# telecommandeB.net
KiCad netlist of a schematic drawn in EAGLE
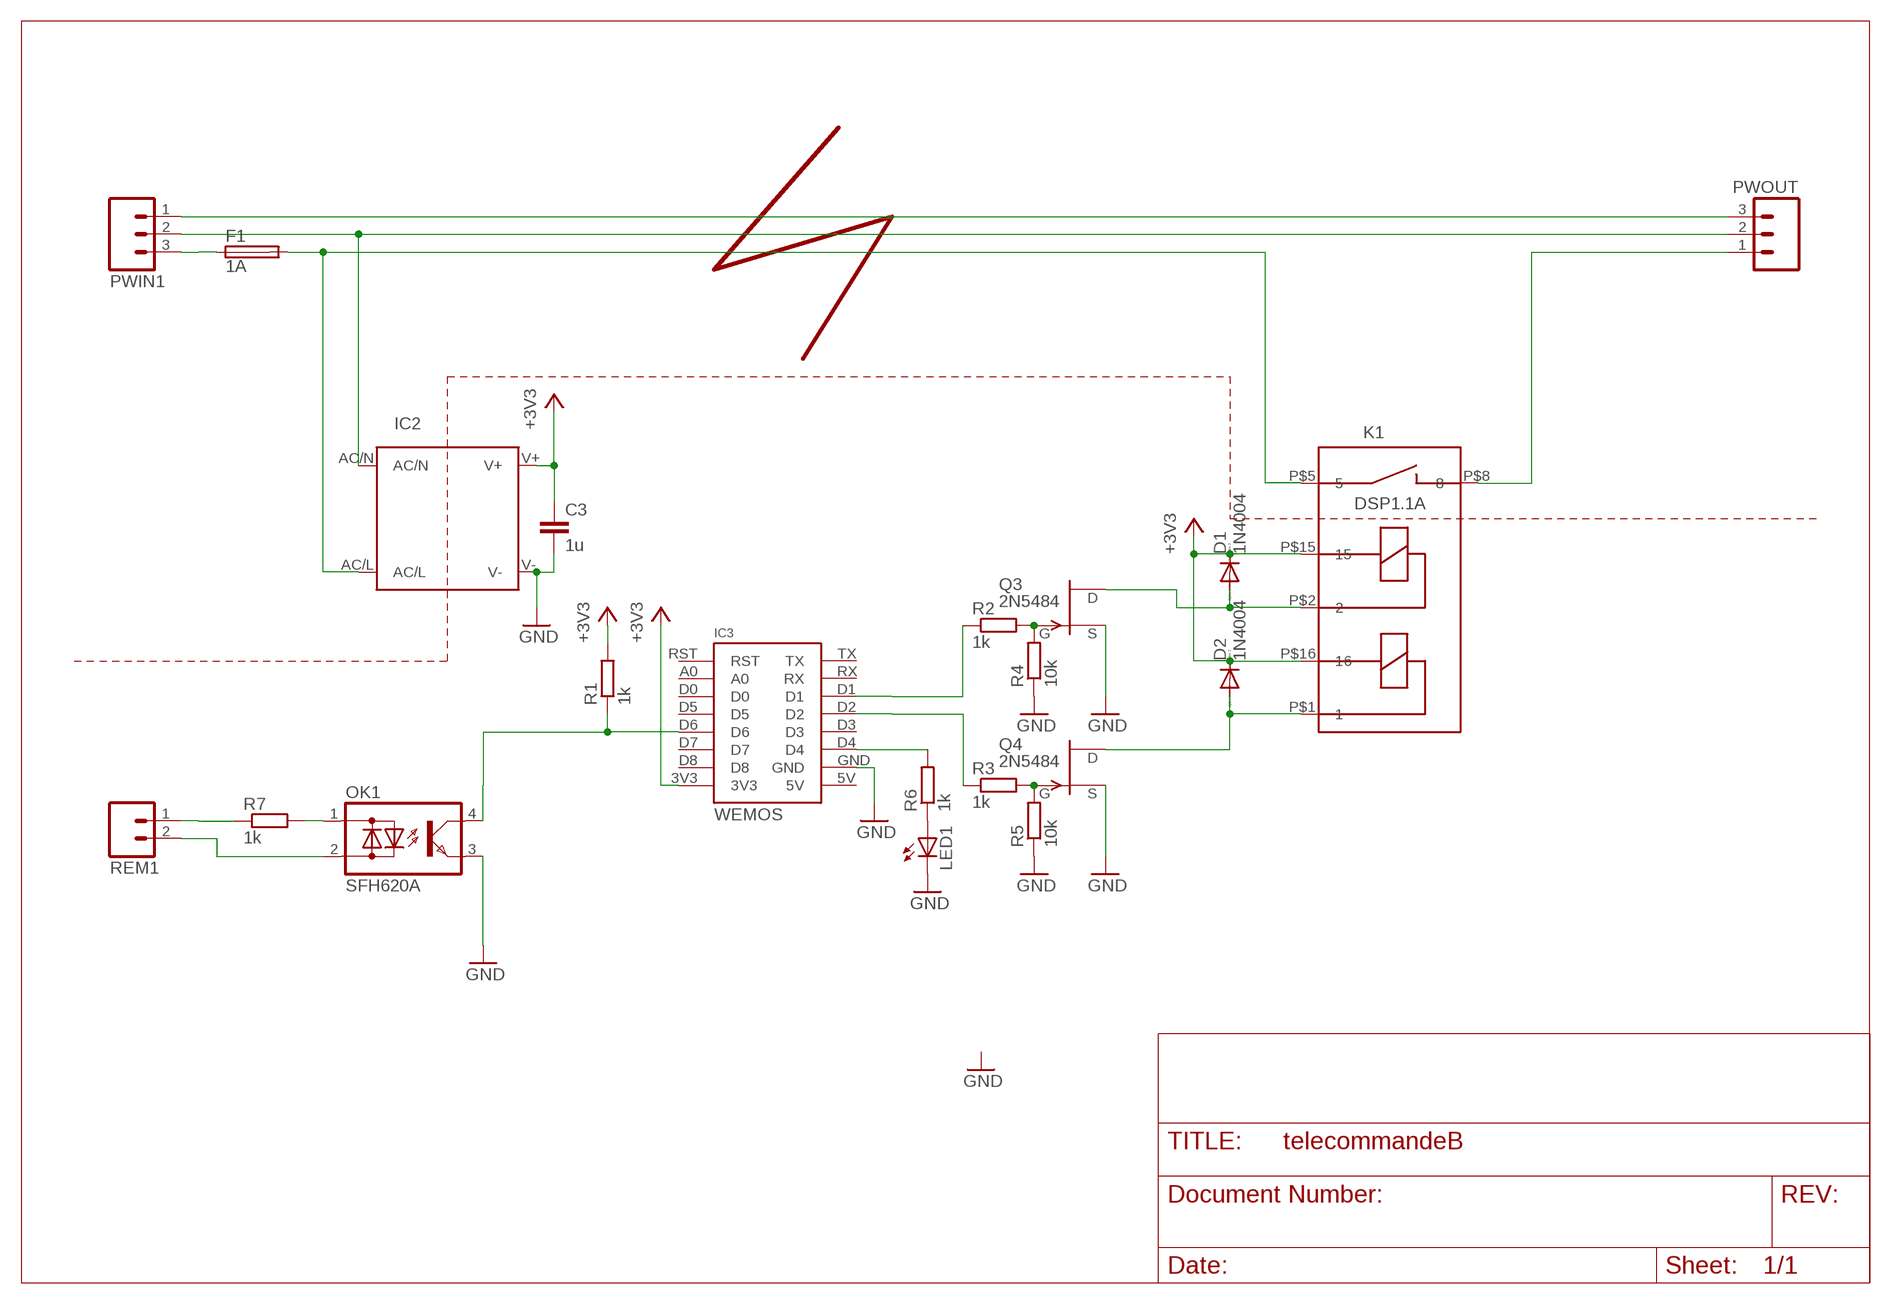
[diagram p0: schematic, sheet 1]

(export (version "E")
  (design (tool "Eeschema 10.0.6"))
  (components
    (comp (ref "C3")
      (value "1u")
      (footprint "eagle-import:C025-024X044")
      (libsource (lib "eagle-import") (part "C-EU025-024X044"))
    )
    (comp (ref "D1")
      (value "1N4004")
      (footprint "eagle-import:DO41-10")
      (libsource (lib "eagle-import") (part "1N4004"))
    )
    (comp (ref "D2")
      (value "1N4004")
      (footprint "eagle-import:DO41-10")
      (libsource (lib "eagle-import") (part "1N4004"))
    )
    (comp (ref "F1")
      (value "1A")
      (footprint "eagle-import:GSH15")
      (fields (field (name "MPN") "64900001039"))
      (libsource (lib "eagle-import") (part "GSH15"))
    )
    (comp (ref "IC2")
      (value "IRM_03")
      (footprint "eagle-import:IRM_03")
      (libsource (lib "eagle-import") (part "IRM_03"))
    )
    (comp (ref "IC3")
      (value "WEMOS")
      (footprint "eagle-import:WEMOS")
      (libsource (lib "eagle-import") (part "WEMOS"))
    )
    (comp (ref "K1")
      (value "DSP1.1A")
      (footprint "eagle-import:DSP1A")
      (libsource (lib "eagle-import") (part "DSP1.1A"))
    )
    (comp (ref "LED1")
      (value "LED3MM")
      (footprint "eagle-import:LED3MM")
      (libsource (lib "eagle-import") (part "LED3MM"))
    )
    (comp (ref "OK1")
      (value "SFH620A")
      (footprint "eagle-import:DIL04")
      (fields (field (name "MPN") "SFH620A-2"))
      (libsource (lib "eagle-import") (part "SFH620A"))
    )
    (comp (ref "PWIN1")
      (value "M03-SCREW-5MM")
      (footprint "eagle-import:SCREWTERMINAL-5MM-3")
      (libsource (lib "eagle-import") (part "M03-SCREW-5MM"))
    )
    (comp (ref "PWOUT")
      (value "M03-SCREW-5MM")
      (footprint "eagle-import:SCREWTERMINAL-5MM-3")
      (libsource (lib "eagle-import") (part "M03-SCREW-5MM"))
    )
    (comp (ref "Q3")
      (value "2N5484")
      (footprint "eagle-import:TO92-")
      (libsource (lib "eagle-import") (part "?5482N4"))
    )
    (comp (ref "Q4")
      (value "2N5484")
      (footprint "eagle-import:TO92-")
      (libsource (lib "eagle-import") (part "?5482N4"))
    )
    (comp (ref "R1")
      (value "1k")
      (footprint "eagle-import:0207_10")
      (libsource (lib "eagle-import") (part "R-EU_0207/10"))
    )
    (comp (ref "R2")
      (value "1k")
      (footprint "eagle-import:0204_7")
      (libsource (lib "eagle-import") (part "R-EU_0204/7"))
    )
    (comp (ref "R3")
      (value "1k")
      (footprint "eagle-import:0204_7")
      (libsource (lib "eagle-import") (part "R-EU_0204/7"))
    )
    (comp (ref "R4")
      (value "10k")
      (footprint "eagle-import:0204_7")
      (libsource (lib "eagle-import") (part "R-EU_0204/7"))
    )
    (comp (ref "R5")
      (value "10k")
      (footprint "eagle-import:0204_7")
      (libsource (lib "eagle-import") (part "R-EU_0204/7"))
    )
    (comp (ref "R6")
      (value "1k")
      (footprint "eagle-import:0204_7")
      (libsource (lib "eagle-import") (part "R-EU_0204/7"))
    )
    (comp (ref "R7")
      (value "1k")
      (footprint "eagle-import:0207_10")
      (libsource (lib "eagle-import") (part "R-EU_0207/10"))
    )
    (comp (ref "REM1")
      (value "M025MM")
      (footprint "eagle-import:SCREWTERMINAL-5MM-2")
      (libsource (lib "eagle-import") (part "M025MM"))
    )
  )
  (nets
    (net (code "1") (name "+3V3") (class "Default")
      (node (ref "C3") (pin "1") (pinfunction "1_1") (pintype "passive"))
      (node (ref "D1") (pin "C") (pinfunction "C_C") (pintype "passive"))
      (node (ref "D2") (pin "C") (pinfunction "C_C") (pintype "passive"))
      (node (ref "IC2") (pin "V+") (pinfunction "V+_V+") (pintype "output"))
      (node (ref "IC3") (pin "3V3") (pinfunction "3V3_3V3") (pintype "bidirectional"))
      (node (ref "K1") (pin "P$15") (pinfunction "15_P$15") (pintype "bidirectional"))
      (node (ref "K1") (pin "P$16") (pinfunction "16_P$16") (pintype "bidirectional"))
      (node (ref "R1") (pin "2") (pinfunction "2_2") (pintype "passive"))
    )
    (net (code "2") (name "GND") (class "Default")
      (node (ref "C3") (pin "2") (pinfunction "2_2") (pintype "passive"))
      (node (ref "IC2") (pin "V-") (pinfunction "V-_V-") (pintype "output"))
      (node (ref "IC3") (pin "GND") (pinfunction "GND_GND") (pintype "bidirectional"))
      (node (ref "LED1") (pin "K") (pinfunction "C_K") (pintype "passive"))
      (node (ref "OK1") (pin "3") (pinfunction "E_3") (pintype "passive"))
      (node (ref "Q3") (pin "2") (pinfunction "S_2") (pintype "passive"))
      (node (ref "Q4") (pin "2") (pinfunction "S_2") (pintype "passive"))
      (node (ref "R4") (pin "1") (pinfunction "1_1") (pintype "passive"))
      (node (ref "R5") (pin "1") (pinfunction "1_1") (pintype "passive"))
    )
    (net (code "3") (name "Net-(F1-Pad1)") (class "Default")
      (node (ref "F1") (pin "1") (pinfunction "1_1") (pintype "passive"))
      (node (ref "PWIN1") (pin "3") (pinfunction "3_3") (pintype "passive"))
    )
    (net (code "4") (name "Net-(IC2-PadAC{slash}N)") (class "Default")
      (node (ref "IC2") (pin "AC/N") (pinfunction "AC/N_AC/N") (pintype "input"))
      (node (ref "PWIN1") (pin "2") (pinfunction "2_2") (pintype "passive"))
      (node (ref "PWOUT") (pin "2") (pinfunction "2_2") (pintype "passive"))
    )
    (net (code "5") (name "Net-(IC3-PadD1)") (class "Default")
      (node (ref "IC3") (pin "D1") (pinfunction "D1_D1") (pintype "bidirectional"))
      (node (ref "R2") (pin "1") (pinfunction "1_1") (pintype "passive"))
    )
    (net (code "6") (name "Net-(IC3-PadD2)") (class "Default")
      (node (ref "IC3") (pin "D2") (pinfunction "D2_D2") (pintype "bidirectional"))
      (node (ref "R3") (pin "1") (pinfunction "1_1") (pintype "passive"))
    )
    (net (code "7") (name "Net-(IC3-PadD4)") (class "Default")
      (node (ref "IC3") (pin "D4") (pinfunction "D4_D4") (pintype "bidirectional"))
      (node (ref "R6") (pin "2") (pinfunction "2_2") (pintype "passive"))
    )
    (net (code "8") (name "Net-(K1-1)") (class "Default")
      (node (ref "D2") (pin "A") (pinfunction "A_A") (pintype "passive"))
      (node (ref "K1") (pin "P$1") (pinfunction "1_P$1") (pintype "bidirectional"))
      (node (ref "Q4") (pin "3") (pinfunction "D_3") (pintype "passive"))
    )
    (net (code "9") (name "Net-(K1-2)") (class "Default")
      (node (ref "D1") (pin "A") (pinfunction "A_A") (pintype "passive"))
      (node (ref "K1") (pin "P$2") (pinfunction "2_P$2") (pintype "bidirectional"))
      (node (ref "Q3") (pin "3") (pinfunction "D_3") (pintype "passive"))
    )
    (net (code "10") (name "Net-(K1-5)") (class "Default")
      (node (ref "F1") (pin "2") (pinfunction "2_2") (pintype "passive"))
      (node (ref "IC2") (pin "AC/L") (pinfunction "AC/L_AC/L") (pintype "input"))
      (node (ref "K1") (pin "P$5") (pinfunction "5_P$5") (pintype "bidirectional"))
    )
    (net (code "11") (name "Net-(K1-8)") (class "Default")
      (node (ref "K1") (pin "P$8") (pinfunction "8_P$8") (pintype "bidirectional"))
      (node (ref "PWOUT") (pin "1") (pinfunction "1_1") (pintype "passive"))
    )
    (net (code "12") (name "Net-(LED1-PadA)") (class "Default")
      (node (ref "LED1") (pin "A") (pinfunction "A_A") (pintype "passive"))
      (node (ref "R6") (pin "1") (pinfunction "1_1") (pintype "passive"))
    )
    (net (code "13") (name "Net-(OK1-AC1)") (class "Default")
      (node (ref "OK1") (pin "1") (pinfunction "AC1_1") (pintype "passive"))
      (node (ref "R7") (pin "2") (pinfunction "2_2") (pintype "passive"))
    )
    (net (code "14") (name "Net-(OK1-AC2)") (class "Default")
      (node (ref "OK1") (pin "2") (pinfunction "AC2_2") (pintype "passive"))
      (node (ref "REM1") (pin "2") (pinfunction "2_2") (pintype "passive"))
    )
    (net (code "15") (name "Net-(OK1-C)") (class "Default")
      (node (ref "IC3") (pin "D6") (pinfunction "D6_D6") (pintype "bidirectional"))
      (node (ref "OK1") (pin "4") (pinfunction "C_4") (pintype "passive"))
      (node (ref "R1") (pin "1") (pinfunction "1_1") (pintype "passive"))
    )
    (net (code "16") (name "Net-(PWIN1-Pad1)") (class "Default")
      (node (ref "PWIN1") (pin "1") (pinfunction "1_1") (pintype "passive"))
      (node (ref "PWOUT") (pin "3") (pinfunction "3_3") (pintype "passive"))
    )
    (net (code "17") (name "Net-(Q3-G)") (class "Default")
      (node (ref "Q3") (pin "1") (pinfunction "G_1") (pintype "passive"))
      (node (ref "R2") (pin "2") (pinfunction "2_2") (pintype "passive"))
      (node (ref "R4") (pin "2") (pinfunction "2_2") (pintype "passive"))
    )
    (net (code "18") (name "Net-(Q4-G)") (class "Default")
      (node (ref "Q4") (pin "1") (pinfunction "G_1") (pintype "passive"))
      (node (ref "R3") (pin "2") (pinfunction "2_2") (pintype "passive"))
      (node (ref "R5") (pin "2") (pinfunction "2_2") (pintype "passive"))
    )
    (net (code "19") (name "Net-(R7-Pad1)") (class "Default")
      (node (ref "R7") (pin "1") (pinfunction "1_1") (pintype "passive"))
      (node (ref "REM1") (pin "1") (pinfunction "1_1") (pintype "passive"))
    )
    (net (code "20") (name "unconnected-(IC3-Pad5V)") (class "Default")
      (node (ref "IC3") (pin "5V") (pinfunction "5V_5V") (pintype "bidirectional"))
    )
    (net (code "21") (name "unconnected-(IC3-PadA0)") (class "Default")
      (node (ref "IC3") (pin "A0") (pinfunction "A0_A0") (pintype "bidirectional"))
    )
    (net (code "22") (name "unconnected-(IC3-PadD0)") (class "Default")
      (node (ref "IC3") (pin "D0") (pinfunction "D0_D0") (pintype "bidirectional"))
    )
    (net (code "23") (name "unconnected-(IC3-PadD3)") (class "Default")
      (node (ref "IC3") (pin "D3") (pinfunction "D3_D3") (pintype "bidirectional"))
    )
    (net (code "24") (name "unconnected-(IC3-PadD5)") (class "Default")
      (node (ref "IC3") (pin "D5") (pinfunction "D5_D5") (pintype "bidirectional"))
    )
    (net (code "25") (name "unconnected-(IC3-PadD7)") (class "Default")
      (node (ref "IC3") (pin "D7") (pinfunction "D7_D7") (pintype "bidirectional"))
    )
    (net (code "26") (name "unconnected-(IC3-PadD8)") (class "Default")
      (node (ref "IC3") (pin "D8") (pinfunction "D8_D8") (pintype "bidirectional"))
    )
    (net (code "27") (name "unconnected-(IC3-PadRST)") (class "Default")
      (node (ref "IC3") (pin "RST") (pinfunction "RST_RST") (pintype "bidirectional"))
    )
    (net (code "28") (name "unconnected-(IC3-PadRX)") (class "Default")
      (node (ref "IC3") (pin "RX") (pinfunction "RX_RX") (pintype "bidirectional"))
    )
    (net (code "29") (name "unconnected-(IC3-PadTX)") (class "Default")
      (node (ref "IC3") (pin "TX") (pinfunction "TX_TX") (pintype "bidirectional"))
    )
  )
)
